# Ref_3V3_LM4132AMF.net
KiCad netlist of a schematic drawn in Altium Designer
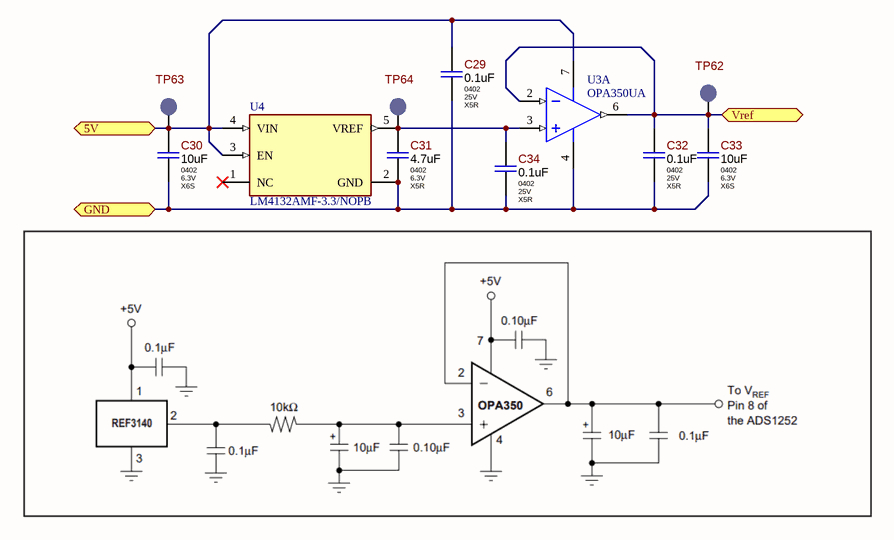
[diagram p0: Ref_3V3_LM4132AMF.SchDoc]

(export (version "E")
  (design (tool "Eeschema 10.0.6"))
  (components
    (comp (ref "C29")
      (value "0.1uF")
      (footprint "C_CERAMIC_0402_MED")
      (description "100nF 25V X5R ±10% 0402 Ceramic Capacitor RoHS")
      (fields
        (field (name "PACKAGE") "0402")
        (field (name "VOLTAGE") "25V")
        (field (name "DIELECTRIC TYPE") "X5R")
        (field (name "PART NUMBER") "CL05A104KA5NNNC")
        (field (name "MANUFACTURER") "Samsung Electro-Mechanics")
      )
      (libsource (lib "EL.XXX.T01") (part "Capacitor-NonPolar"))
    )
    (comp (ref "C30")
      (value "10uF")
      (footprint "C_CERAMIC_0402_MED")
      (description "10uF 6.3V X6S ±20% 0402 Ceramic Capacitor RoHS")
      (fields
        (field (name "PACKAGE") "0402")
        (field (name "VOLTAGE") "6.3V")
        (field (name "DIELECTRIC TYPE") "X6S")
        (field (name "PART NUMBER") "GRM155C80J106ME11D")
        (field (name "MANUFACTURER") "Murata Electronics")
      )
      (libsource (lib "EL.XXX.T01") (part "Capacitor-NonPolar"))
    )
    (comp (ref "C31")
      (value "4.7uF")
      (footprint "C_CERAMIC_0402_MED")
      (description "4.7uF 6.3V X5R ±20% 0402 Ceramic Capacitor RoHS")
      (fields
        (field (name "PACKAGE") "0402")
        (field (name "VOLTAGE") "6.3V")
        (field (name "DIELECTRIC TYPE") "X5R")
        (field (name "PART NUMBER") "GRM155R60J475ME47")
        (field (name "MANUFACTURER") "Murata Electronics")
      )
      (libsource (lib "EL.XXX.T01") (part "Capacitor-NonPolar"))
    )
    (comp (ref "C32")
      (value "0.1uF")
      (footprint "C_CERAMIC_0402_MED")
      (description "100nF 25V X5R ±10% 0402 Ceramic Capacitor RoHS")
      (fields
        (field (name "PACKAGE") "0402")
        (field (name "VOLTAGE") "25V")
        (field (name "DIELECTRIC TYPE") "X5R")
        (field (name "PART NUMBER") "CL05A104KA5NNNC")
        (field (name "MANUFACTURER") "Samsung Electro-Mechanics")
      )
      (libsource (lib "EL.XXX.T01") (part "Capacitor-NonPolar"))
    )
    (comp (ref "C33")
      (value "10uF")
      (footprint "C_CERAMIC_0402_MED")
      (description "10uF 6.3V X6S ±20% 0402 Ceramic Capacitor RoHS")
      (fields
        (field (name "PACKAGE") "0402")
        (field (name "VOLTAGE") "6.3V")
        (field (name "DIELECTRIC TYPE") "X6S")
        (field (name "PART NUMBER") "GRM155C80J106ME11D")
        (field (name "MANUFACTURER") "Murata Electronics")
      )
      (libsource (lib "EL.XXX.T01") (part "Capacitor-NonPolar"))
    )
    (comp (ref "C34")
      (value "0.1uF")
      (footprint "C_CERAMIC_0402_MED")
      (description "100nF 25V X5R ±10% 0402 Ceramic Capacitor RoHS")
      (fields
        (field (name "PACKAGE") "0402")
        (field (name "VOLTAGE") "25V")
        (field (name "DIELECTRIC TYPE") "X5R")
        (field (name "PART NUMBER") "CL05A104KA5NNNC")
        (field (name "MANUFACTURER") "Samsung Electro-Mechanics")
      )
      (libsource (lib "EL.XXX.T01") (part "Capacitor-NonPolar"))
    )
    (comp (ref "TP62")
      (value "LED_LINK")
      (footprint "TP_SMD_2mm")
      (description "Test Point SMD Pad 1.0mm/1.5mm/2mm")
      (fields (field (name "PART NUMBER") "TP-PAD-SMD"))
      (libsource (lib "EL.XXX.T01") (part "Test-Point-SMD-1"))
    )
    (comp (ref "TP63")
      (value "LED_LINK")
      (footprint "TP_SMD_2mm")
      (description "Test Point SMD Pad 1.0mm/1.5mm/2mm")
      (fields (field (name "PART NUMBER") "TP-PAD-SMD"))
      (libsource (lib "EL.XXX.T01") (part "Test-Point-SMD-1"))
    )
    (comp (ref "TP64")
      (value "LED_LINK")
      (footprint "TP_SMD_2mm")
      (description "Test Point SMD Pad 1.0mm/1.5mm/2mm")
      (fields (field (name "PART NUMBER") "TP-PAD-SMD"))
      (libsource (lib "EL.XXX.T01") (part "Test-Point-SMD-1"))
    )
    (comp (ref "U3")
      (value "OPA350UA")
      (footprint "D0008A_M")
      (fields (field (name "MANUFACTURER") "Texas Instruments"))
      (libsource (lib "EL.XXX.T01") (part "TI-OPA-8_1"))
    )
    (comp (ref "U4")
      (value "LM4132AMF-3.3/NOPB")
      (footprint "SOT-23-5")
      (description "IC VREF SERIES 0.05% SOT23-5")
      (fields (field (name "TOLERANCE") "0.05%"))
      (libsource (lib "EL.XXX.T01") (part "LM4132AMF-3.3/NOPB"))
    )
  )
  (nets
    (net (code "1") (name "/5V") (class "Default")
      (node (ref "C29") (pin "1") (pinfunction "1_1") (pintype "passive"))
      (node (ref "C30") (pin "1") (pinfunction "1_1") (pintype "passive"))
      (node (ref "TP63") (pin "1") (pintype "passive"))
      (node (ref "U3") (pin "7") (pinfunction "V+_7") (pintype "power_in"))
      (node (ref "U4") (pin "3") (pinfunction "EN_3") (pintype "input"))
      (node (ref "U4") (pin "4") (pinfunction "VIN_4") (pintype "input"))
    )
    (net (code "2") (name "/GND") (class "Default")
      (node (ref "C29") (pin "2") (pinfunction "2_2") (pintype "passive"))
      (node (ref "C30") (pin "2") (pinfunction "2_2") (pintype "passive"))
      (node (ref "C31") (pin "2") (pinfunction "2_2") (pintype "passive"))
      (node (ref "C32") (pin "2") (pinfunction "2_2") (pintype "passive"))
      (node (ref "C33") (pin "2") (pinfunction "2_2") (pintype "passive"))
      (node (ref "C34") (pin "2") (pinfunction "2_2") (pintype "passive"))
      (node (ref "U3") (pin "4") (pinfunction "V-_4") (pintype "power_in"))
      (node (ref "U4") (pin "2") (pinfunction "GND_2") (pintype "power_in"))
    )
    (net (code "3") (name "/Vref") (class "Default")
      (node (ref "C32") (pin "1") (pinfunction "1_1") (pintype "passive"))
      (node (ref "C33") (pin "1") (pinfunction "1_1") (pintype "passive"))
      (node (ref "TP62") (pin "1") (pintype "passive"))
      (node (ref "U3") (pin "2") (pinfunction "IN-_2") (pintype "input"))
      (node (ref "U3") (pin "6") (pinfunction "OUT_6") (pintype "output"))
    )
    (net (code "4") (name "Net-(U3A-IN+)") (class "Default")
      (node (ref "C31") (pin "1") (pinfunction "1_1") (pintype "passive"))
      (node (ref "C34") (pin "1") (pinfunction "1_1") (pintype "passive"))
      (node (ref "TP64") (pin "1") (pintype "passive"))
      (node (ref "U3") (pin "3") (pinfunction "IN+_3") (pintype "input"))
      (node (ref "U4") (pin "5") (pinfunction "VREF_5") (pintype "output"))
    )
    (net (code "5") (name "unconnected-(U4-NC-Pad1)") (class "Default")
      (node (ref "U4") (pin "1") (pinfunction "NC_1") (pintype "passive+no_connect"))
    )
  )
)
